# ADE7753.net
KiCad netlist of a schematic drawn in Altium Designer
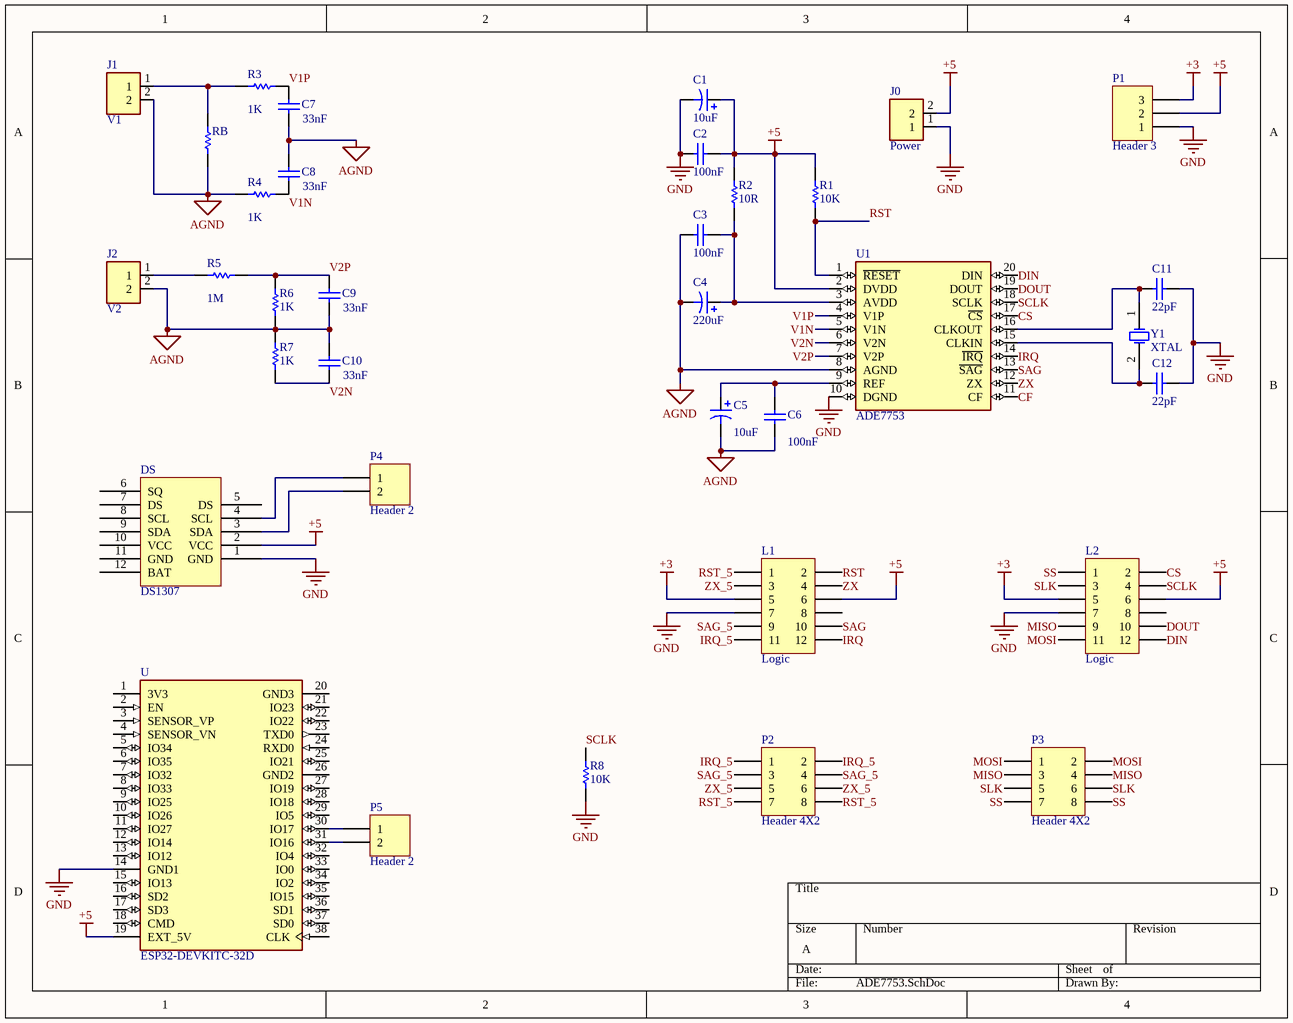
[diagram p0: ADE7753.SchDoc]

(export (version "E")
  (design (tool "Eeschema 10.0.6"))
  (components
    (comp (ref "C1")
      (value "10uF")
      (footprint "Tu hóa 10uF 50v")
      (description "Polarized Capacitor (Radial)")
      (fields (field (name "Comment") "Cap Pol1") (field (name "PUBLISHER") "Altium Limited"))
      (libsource (lib "Miscellaneous Devices") (part "Cap Pol1"))
    )
    (comp (ref "C2")
      (value "100nF")
      (footprint "Tu Gom")
      (description "Capacitor")
      (fields (field (name "Comment") "Cap") (field (name "PUBLISHER") "Altium Limited"))
      (libsource (lib "Miscellaneous Devices") (part "Cap"))
    )
    (comp (ref "C3")
      (value "100nF")
      (footprint "Tu Gom")
      (description "Capacitor")
      (fields (field (name "Comment") "Cap") (field (name "PUBLISHER") "Altium Limited"))
      (libsource (lib "Miscellaneous Devices") (part "Cap"))
    )
    (comp (ref "C4")
      (value "220uF")
      (footprint "Tu hóa 10uF 50v")
      (description "Polarized Capacitor (Radial)")
      (fields (field (name "Comment") "Cap Pol1") (field (name "PUBLISHER") "Altium Limited"))
      (libsource (lib "Miscellaneous Devices") (part "Cap Pol1"))
    )
    (comp (ref "C5")
      (value "10uF")
      (footprint "Tu hóa 10uF 50v")
      (description "Polarized Capacitor (Radial)")
      (fields (field (name "Comment") "Cap Pol1") (field (name "PUBLISHER") "Altium Limited"))
      (libsource (lib "Miscellaneous Devices") (part "Cap Pol1"))
    )
    (comp (ref "C6")
      (value "100nF")
      (footprint "Tu Gom")
      (description "Capacitor")
      (fields (field (name "Comment") "Cap") (field (name "PUBLISHER") "Altium Limited"))
      (libsource (lib "Miscellaneous Devices") (part "Cap"))
    )
    (comp (ref "C7")
      (value "33nF")
      (footprint "Tu Gom")
      (description "Capacitor")
      (fields (field (name "Comment") "Cap") (field (name "PUBLISHER") "Altium Limited"))
      (libsource (lib "Miscellaneous Devices") (part "Cap"))
    )
    (comp (ref "C8")
      (value "33nF")
      (footprint "Tu Gom")
      (description "Capacitor")
      (fields (field (name "Comment") "Cap") (field (name "PUBLISHER") "Altium Limited"))
      (libsource (lib "Miscellaneous Devices") (part "Cap"))
    )
    (comp (ref "C9")
      (value "33nF")
      (footprint "Tu Gom")
      (description "Capacitor")
      (fields (field (name "Comment") "Cap") (field (name "PUBLISHER") "Altium Limited"))
      (libsource (lib "Miscellaneous Devices") (part "Cap"))
    )
    (comp (ref "C10")
      (value "33nF")
      (footprint "Tu Gom")
      (description "Capacitor")
      (fields (field (name "Comment") "Cap") (field (name "PUBLISHER") "Altium Limited"))
      (libsource (lib "Miscellaneous Devices") (part "Cap"))
    )
    (comp (ref "C11")
      (value "22pF")
      (footprint "Tu Gom")
      (description "Capacitor")
      (fields (field (name "Comment") "Cap") (field (name "PUBLISHER") "Altium Limited"))
      (libsource (lib "Miscellaneous Devices") (part "Cap"))
    )
    (comp (ref "C12")
      (value "22pF")
      (footprint "Tu Gom")
      (description "Capacitor")
      (fields (field (name "Comment") "Cap") (field (name "PUBLISHER") "Altium Limited"))
      (libsource (lib "Miscellaneous Devices") (part "Cap"))
    )
    (comp (ref "DS")
      (value "DS1307")
      (footprint "PCBComponent_1")
      (libsource (lib "DS1307") (part "Component_1"))
    )
    (comp (ref "J0")
      (value "Power")
      (footprint "CONN_282836-2")
      (description "TERM BLOCK 2POS SIDE ENTRY 5MM")
      (fields (field (name "MF") "{'manufacturer': u'TE Connectivity'}") (field (name "MP") "282836-2"))
      (libsource (lib "") (part "282836-2_1"))
    )
    (comp (ref "J1")
      (value "V1")
      (footprint "CONN_282836-2")
      (description "TERM BLOCK 2POS SIDE ENTRY 5MM")
      (fields (field (name "MF") "{'manufacturer': u'TE Connectivity'}") (field (name "MP") "282836-2"))
      (libsource (lib "SnapEDA_Library") (part "282836-2"))
    )
    (comp (ref "J2")
      (value "V2")
      (footprint "CONN_282836-2")
      (description "TERM BLOCK 2POS SIDE ENTRY 5MM")
      (fields (field (name "MF") "{'manufacturer': u'TE Connectivity'}") (field (name "MP") "282836-2"))
      (libsource (lib "SnapEDA_Library") (part "282836-2"))
    )
    (comp (ref "L1")
      (value "Logic")
      (footprint "Logic level 3-5")
      (description "Header, 6-Pin, Dual row")
      (fields (field (name "PUBLISHER") "Altium Limited"))
      (libsource (lib "Miscellaneous Connectors") (part "Header 6X2"))
    )
    (comp (ref "L2")
      (value "Logic")
      (footprint "Logic level 3-5")
      (description "Header, 6-Pin, Dual row")
      (fields (field (name "PUBLISHER") "Altium Limited"))
      (libsource (lib "Miscellaneous Connectors") (part "Header 6X2"))
    )
    (comp (ref "P1")
      (value "Header 3")
      (footprint "HDR1X3")
      (description "Header, 3-Pin")
      (fields (field (name "PUBLISHER") "Altium Limited"))
      (libsource (lib "Miscellaneous Connectors") (part "Header 3"))
    )
    (comp (ref "P2")
      (value "Header 4X2")
      (footprint "HDR2X4")
      (description "Header, 4-Pin, Dual row")
      (fields (field (name "PUBLISHER") "Altium Limited"))
      (libsource (lib "Miscellaneous Connectors") (part "Header 4X2"))
    )
    (comp (ref "P3")
      (value "Header 4X2")
      (footprint "HDR2X4")
      (description "Header, 4-Pin, Dual row")
      (fields (field (name "PUBLISHER") "Altium Limited"))
      (libsource (lib "Miscellaneous Connectors") (part "Header 4X2"))
    )
    (comp (ref "P4")
      (value "Header 2")
      (footprint "HDR1X2")
      (description "Header, 2-Pin")
      (fields (field (name "PUBLISHER") "Altium Limited"))
      (libsource (lib "Miscellaneous Connectors") (part "Header 2"))
    )
    (comp (ref "P5")
      (value "Header 2")
      (footprint "HDR1X2")
      (description "Header, 2-Pin")
      (fields (field (name "PUBLISHER") "Altium Limited"))
      (libsource (lib "Miscellaneous Connectors") (part "Header 2"))
    )
    (comp (ref "R1")
      (value "10K")
      (footprint "AXIAL-0.3")
      (description "Resistor")
      (fields (field (name "Comment") "Res1") (field (name "PUBLISHER") "Altium Limited"))
      (libsource (lib "Miscellaneous Devices") (part "Res1"))
    )
    (comp (ref "R2")
      (value "10R")
      (footprint "AXIAL-0.3")
      (description "Resistor")
      (fields (field (name "Comment") "Res1") (field (name "PUBLISHER") "Altium Limited"))
      (libsource (lib "Miscellaneous Devices") (part "Res1"))
    )
    (comp (ref "R3")
      (value "1K")
      (footprint "AXIAL-0.3")
      (description "Resistor")
      (fields (field (name "Comment") "Res1") (field (name "PUBLISHER") "Altium Limited"))
      (libsource (lib "Miscellaneous Devices") (part "Res1"))
    )
    (comp (ref "R4")
      (value "1K")
      (footprint "AXIAL-0.3")
      (description "Resistor")
      (fields (field (name "Comment") "Res1") (field (name "PUBLISHER") "Altium Limited"))
      (libsource (lib "Miscellaneous Devices") (part "Res1"))
    )
    (comp (ref "R5")
      (value "1M")
      (footprint "AXIAL-0.3")
      (description "Resistor")
      (fields (field (name "Comment") "Res1") (field (name "PUBLISHER") "Altium Limited"))
      (libsource (lib "Miscellaneous Devices") (part "Res1"))
    )
    (comp (ref "R6")
      (value "1K")
      (footprint "AXIAL-0.3")
      (description "Resistor")
      (fields (field (name "Comment") "Res1") (field (name "PUBLISHER") "Altium Limited"))
      (libsource (lib "Miscellaneous Devices") (part "Res1"))
    )
    (comp (ref "R7")
      (value "1K")
      (footprint "AXIAL-0.3")
      (description "Resistor")
      (fields (field (name "Comment") "Res1") (field (name "PUBLISHER") "Altium Limited"))
      (libsource (lib "Miscellaneous Devices") (part "Res1"))
    )
    (comp (ref "R8")
      (value "10K")
      (footprint "AXIAL-0.3")
      (description "Resistor")
      (fields (field (name "Comment") "Res1") (field (name "PUBLISHER") "Altium Limited"))
      (libsource (lib "Miscellaneous Devices") (part "Res1"))
    )
    (comp (ref "RB")
      (value "Res1")
      (footprint "AXIAL-0.3")
      (description "Resistor")
      (fields (field (name "PUBLISHER") "Altium Limited"))
      (libsource (lib "Miscellaneous Devices") (part "Res1"))
    )
    (comp (ref "U")
      (value "ESP32-DEVKITC-32D")
      (footprint "MODULE_ESP32-DEVKITC-32D")
      (fields (field (name "MF") "Espressif Systems"))
      (libsource (lib "ESP32-DEVKITC-32D") (part "ESP32-DEVKITC-32D"))
    )
    (comp (ref "U1")
      (value "ADE7753")
      (footprint "ADE_Header")
      (description "Single-Phase Multifunction Metering IC")
      (fields (field (name "MF") "{'manufacturer': u'Analog Devices'}"))
      (libsource (lib "SnapEDA_Library") (part "ADE7753"))
    )
    (comp (ref "Y1")
      (value "XTAL")
      (footprint "3.5795 mhz crystal")
      (description "Crystal Oscillator")
      (fields (field (name "PUBLISHER") "Altium Limited"))
      (libsource (lib "Miscellaneous Devices") (part "XTAL"))
    )
  )
  (nets
    (net (code "1") (name "+3") (class "Default")
      (node (ref "L1") (pin "5") (pinfunction "5_5") (pintype "passive"))
      (node (ref "L2") (pin "5") (pinfunction "5_5") (pintype "passive"))
      (node (ref "P1") (pin "3") (pinfunction "3_3") (pintype "passive"))
    )
    (net (code "2") (name "+5") (class "Default")
      (node (ref "C1") (pin "1") (pinfunction "1_1") (pintype "passive"))
      (node (ref "C2") (pin "1") (pinfunction "1_1") (pintype "passive"))
      (node (ref "DS") (pin "2") (pinfunction "VCC_2") (pintype "passive"))
      (node (ref "J0") (pin "2") (pinfunction "2_2") (pintype "passive"))
      (node (ref "L1") (pin "6") (pinfunction "6_6") (pintype "passive"))
      (node (ref "L2") (pin "6") (pinfunction "6_6") (pintype "passive"))
      (node (ref "P1") (pin "2") (pinfunction "2_2") (pintype "passive"))
      (node (ref "R1") (pin "2") (pinfunction "2_2") (pintype "passive"))
      (node (ref "R2") (pin "2") (pinfunction "2_2") (pintype "passive"))
      (node (ref "U") (pin "19") (pinfunction "EXT_5V_19") (pintype "power_in"))
      (node (ref "U1") (pin "2") (pinfunction "DVDD_2") (pintype "bidirectional"))
    )
    (net (code "3") (name "/CF") (class "Default")
      (node (ref "U1") (pin "11") (pinfunction "CF_11") (pintype "bidirectional"))
    )
    (net (code "4") (name "/CS") (class "Default")
      (node (ref "L2") (pin "2") (pinfunction "2_2") (pintype "passive"))
      (node (ref "U1") (pin "17") (pinfunction "~{CS}_17") (pintype "bidirectional"))
    )
    (net (code "5") (name "/DIN") (class "Default")
      (node (ref "L2") (pin "12") (pinfunction "12_12") (pintype "passive"))
      (node (ref "U1") (pin "20") (pinfunction "DIN_20") (pintype "bidirectional"))
    )
    (net (code "6") (name "/DOUT") (class "Default")
      (node (ref "L2") (pin "10") (pinfunction "10_10") (pintype "passive"))
      (node (ref "U1") (pin "19") (pinfunction "DOUT_19") (pintype "bidirectional"))
    )
    (net (code "7") (name "/IRQ") (class "Default")
      (node (ref "L1") (pin "12") (pinfunction "12_12") (pintype "passive"))
      (node (ref "U1") (pin "14") (pinfunction "~{IRQ}_14") (pintype "bidirectional"))
    )
    (net (code "8") (name "/IRQ_5") (class "Default")
      (node (ref "L1") (pin "11") (pinfunction "11_11") (pintype "passive"))
      (node (ref "P2") (pin "1") (pinfunction "1_1") (pintype "passive"))
      (node (ref "P2") (pin "2") (pinfunction "2_2") (pintype "passive"))
    )
    (net (code "9") (name "/MISO") (class "Default")
      (node (ref "L2") (pin "9") (pinfunction "9_9") (pintype "passive"))
      (node (ref "P3") (pin "3") (pinfunction "3_3") (pintype "passive"))
      (node (ref "P3") (pin "4") (pinfunction "4_4") (pintype "passive"))
    )
    (net (code "10") (name "/MOSI") (class "Default")
      (node (ref "L2") (pin "11") (pinfunction "11_11") (pintype "passive"))
      (node (ref "P3") (pin "1") (pinfunction "1_1") (pintype "passive"))
      (node (ref "P3") (pin "2") (pinfunction "2_2") (pintype "passive"))
    )
    (net (code "11") (name "/RST") (class "Default")
      (node (ref "L1") (pin "2") (pinfunction "2_2") (pintype "passive"))
      (node (ref "R1") (pin "1") (pinfunction "1_1") (pintype "passive"))
      (node (ref "U1") (pin "1") (pinfunction "~{RESET}_1") (pintype "bidirectional"))
    )
    (net (code "12") (name "/RST_5") (class "Default")
      (node (ref "L1") (pin "1") (pinfunction "1_1") (pintype "passive"))
      (node (ref "P2") (pin "7") (pinfunction "7_7") (pintype "passive"))
      (node (ref "P2") (pin "8") (pinfunction "8_8") (pintype "passive"))
    )
    (net (code "13") (name "/SAG") (class "Default")
      (node (ref "L1") (pin "10") (pinfunction "10_10") (pintype "passive"))
      (node (ref "U1") (pin "13") (pinfunction "~{SAG}_13") (pintype "bidirectional"))
    )
    (net (code "14") (name "/SAG_5") (class "Default")
      (node (ref "L1") (pin "9") (pinfunction "9_9") (pintype "passive"))
      (node (ref "P2") (pin "3") (pinfunction "3_3") (pintype "passive"))
      (node (ref "P2") (pin "4") (pinfunction "4_4") (pintype "passive"))
    )
    (net (code "15") (name "/SCLK") (class "Default")
      (node (ref "L2") (pin "4") (pinfunction "4_4") (pintype "passive"))
      (node (ref "R8") (pin "2") (pinfunction "2_2") (pintype "passive"))
      (node (ref "U1") (pin "18") (pinfunction "SCLK_18") (pintype "bidirectional"))
    )
    (net (code "16") (name "/SLK") (class "Default")
      (node (ref "L2") (pin "3") (pinfunction "3_3") (pintype "passive"))
      (node (ref "P3") (pin "5") (pinfunction "5_5") (pintype "passive"))
      (node (ref "P3") (pin "6") (pinfunction "6_6") (pintype "passive"))
    )
    (net (code "17") (name "/SS") (class "Default")
      (node (ref "L2") (pin "1") (pinfunction "1_1") (pintype "passive"))
      (node (ref "P3") (pin "7") (pinfunction "7_7") (pintype "passive"))
      (node (ref "P3") (pin "8") (pinfunction "8_8") (pintype "passive"))
    )
    (net (code "18") (name "/V1N") (class "Default")
      (node (ref "C8") (pin "1") (pinfunction "1_1") (pintype "passive"))
      (node (ref "R4") (pin "2") (pinfunction "2_2") (pintype "passive"))
      (node (ref "U1") (pin "5") (pinfunction "V1N_5") (pintype "bidirectional"))
    )
    (net (code "19") (name "/V1P") (class "Default")
      (node (ref "C7") (pin "2") (pinfunction "2_2") (pintype "passive"))
      (node (ref "R3") (pin "2") (pinfunction "2_2") (pintype "passive"))
      (node (ref "U1") (pin "4") (pinfunction "V1P_4") (pintype "bidirectional"))
    )
    (net (code "20") (name "/V2N") (class "Default")
      (node (ref "C10") (pin "1") (pinfunction "1_1") (pintype "passive"))
      (node (ref "R7") (pin "1") (pinfunction "1_1") (pintype "passive"))
      (node (ref "U1") (pin "6") (pinfunction "V2N_6") (pintype "bidirectional"))
    )
    (net (code "21") (name "/V2P") (class "Default")
      (node (ref "C9") (pin "2") (pinfunction "2_2") (pintype "passive"))
      (node (ref "R5") (pin "2") (pinfunction "2_2") (pintype "passive"))
      (node (ref "R6") (pin "2") (pinfunction "2_2") (pintype "passive"))
      (node (ref "U1") (pin "7") (pinfunction "V2P_7") (pintype "bidirectional"))
    )
    (net (code "22") (name "/ZX") (class "Default")
      (node (ref "L1") (pin "4") (pinfunction "4_4") (pintype "passive"))
      (node (ref "U1") (pin "12") (pinfunction "ZX_12") (pintype "bidirectional"))
    )
    (net (code "23") (name "/ZX_5") (class "Default")
      (node (ref "L1") (pin "3") (pinfunction "3_3") (pintype "passive"))
      (node (ref "P2") (pin "5") (pinfunction "5_5") (pintype "passive"))
      (node (ref "P2") (pin "6") (pinfunction "6_6") (pintype "passive"))
    )
    (net (code "24") (name "AGND") (class "Default")
      (node (ref "C10") (pin "2") (pinfunction "2_2") (pintype "passive"))
      (node (ref "C3") (pin "2") (pinfunction "2_2") (pintype "passive"))
      (node (ref "C4") (pin "2") (pinfunction "2_2") (pintype "passive"))
      (node (ref "C5") (pin "2") (pinfunction "2_2") (pintype "passive"))
      (node (ref "C6") (pin "1") (pinfunction "1_1") (pintype "passive"))
      (node (ref "C7") (pin "1") (pinfunction "1_1") (pintype "passive"))
      (node (ref "C8") (pin "2") (pinfunction "2_2") (pintype "passive"))
      (node (ref "C9") (pin "1") (pinfunction "1_1") (pintype "passive"))
      (node (ref "J1") (pin "2") (pinfunction "2_2") (pintype "passive"))
      (node (ref "J2") (pin "2") (pinfunction "2_2") (pintype "passive"))
      (node (ref "R4") (pin "1") (pinfunction "1_1") (pintype "passive"))
      (node (ref "R6") (pin "1") (pinfunction "1_1") (pintype "passive"))
      (node (ref "R7") (pin "2") (pinfunction "2_2") (pintype "passive"))
      (node (ref "RB") (pin "1") (pinfunction "1_1") (pintype "passive"))
      (node (ref "U1") (pin "8") (pinfunction "AGND_8") (pintype "bidirectional"))
    )
    (net (code "25") (name "GND") (class "Default")
      (node (ref "C1") (pin "2") (pinfunction "2_2") (pintype "passive"))
      (node (ref "C11") (pin "1") (pinfunction "1_1") (pintype "passive"))
      (node (ref "C12") (pin "1") (pinfunction "1_1") (pintype "passive"))
      (node (ref "C2") (pin "2") (pinfunction "2_2") (pintype "passive"))
      (node (ref "DS") (pin "1") (pinfunction "GND_1") (pintype "passive"))
      (node (ref "J0") (pin "1") (pinfunction "1_1") (pintype "passive"))
      (node (ref "L1") (pin "7") (pinfunction "7_7") (pintype "passive"))
      (node (ref "L2") (pin "7") (pinfunction "7_7") (pintype "passive"))
      (node (ref "P1") (pin "1") (pinfunction "1_1") (pintype "passive"))
      (node (ref "R8") (pin "1") (pinfunction "1_1") (pintype "passive"))
      (node (ref "U") (pin "14") (pinfunction "GND1_14") (pintype "power_in"))
      (node (ref "U1") (pin "10") (pinfunction "DGND_10") (pintype "bidirectional"))
    )
    (net (code "26") (name "Net-(DS-SCL-Pad4)") (class "Default")
      (node (ref "DS") (pin "4") (pinfunction "SCL_4") (pintype "passive"))
      (node (ref "P4") (pin "1") (pinfunction "1_1") (pintype "passive"))
    )
    (net (code "27") (name "Net-(DS-SDA-Pad3)") (class "Default")
      (node (ref "DS") (pin "3") (pinfunction "SDA_3") (pintype "passive"))
      (node (ref "P4") (pin "2") (pinfunction "2_2") (pintype "passive"))
    )
    (net (code "28") (name "Net-(J1-Pad1)") (class "Default")
      (node (ref "J1") (pin "1") (pinfunction "1_1") (pintype "passive"))
      (node (ref "R3") (pin "1") (pinfunction "1_1") (pintype "passive"))
      (node (ref "RB") (pin "2") (pinfunction "2_2") (pintype "passive"))
    )
    (net (code "29") (name "Net-(J2-Pad1)") (class "Default")
      (node (ref "J2") (pin "1") (pinfunction "1_1") (pintype "passive"))
      (node (ref "R5") (pin "1") (pinfunction "1_1") (pintype "passive"))
    )
    (net (code "30") (name "Net-(U-IO16)") (class "Default")
      (node (ref "P5") (pin "2") (pinfunction "2_2") (pintype "passive"))
      (node (ref "U") (pin "31") (pinfunction "IO16_31") (pintype "bidirectional"))
    )
    (net (code "31") (name "Net-(U-IO17)") (class "Default")
      (node (ref "P5") (pin "1") (pinfunction "1_1") (pintype "passive"))
      (node (ref "U") (pin "30") (pinfunction "IO17_30") (pintype "bidirectional"))
    )
    (net (code "32") (name "Net-(U1-AVDD)") (class "Default")
      (node (ref "C3") (pin "1") (pinfunction "1_1") (pintype "passive"))
      (node (ref "C4") (pin "1") (pinfunction "1_1") (pintype "passive"))
      (node (ref "R2") (pin "1") (pinfunction "1_1") (pintype "passive"))
      (node (ref "U1") (pin "3") (pinfunction "AVDD_3") (pintype "bidirectional"))
    )
    (net (code "33") (name "Net-(U1-CLKIN)") (class "Default")
      (node (ref "C12") (pin "2") (pinfunction "2_2") (pintype "passive"))
      (node (ref "U1") (pin "15") (pinfunction "CLKIN_15") (pintype "bidirectional"))
      (node (ref "Y1") (pin "2") (pinfunction "OSC2_2") (pintype "passive"))
    )
    (net (code "34") (name "Net-(U1-CLKOUT)") (class "Default")
      (node (ref "C11") (pin "2") (pinfunction "2_2") (pintype "passive"))
      (node (ref "U1") (pin "16") (pinfunction "CLKOUT_16") (pintype "bidirectional"))
      (node (ref "Y1") (pin "1") (pinfunction "OSC1_1") (pintype "passive"))
    )
    (net (code "35") (name "Net-(U1-REF)") (class "Default")
      (node (ref "C5") (pin "1") (pinfunction "1_1") (pintype "passive"))
      (node (ref "C6") (pin "2") (pinfunction "2_2") (pintype "passive"))
      (node (ref "U1") (pin "9") (pinfunction "REF_9") (pintype "bidirectional"))
    )
    (net (code "36") (name "unconnected-(DS-BAT-Pad12)") (class "Default")
      (node (ref "DS") (pin "12") (pinfunction "BAT_12") (pintype "passive"))
    )
    (net (code "37") (name "unconnected-(DS-DS-Pad5)") (class "Default")
      (node (ref "DS") (pin "5") (pinfunction "DS_5") (pintype "passive"))
    )
    (net (code "38") (name "unconnected-(DS-DS-Pad7)") (class "Default")
      (node (ref "DS") (pin "7") (pinfunction "DS_7") (pintype "passive"))
    )
    (net (code "39") (name "unconnected-(DS-GND-Pad11)") (class "Default")
      (node (ref "DS") (pin "11") (pinfunction "GND_11") (pintype "passive"))
    )
    (net (code "40") (name "unconnected-(DS-SCL-Pad8)") (class "Default")
      (node (ref "DS") (pin "8") (pinfunction "SCL_8") (pintype "passive"))
    )
    (net (code "41") (name "unconnected-(DS-SDA-Pad9)") (class "Default")
      (node (ref "DS") (pin "9") (pinfunction "SDA_9") (pintype "passive"))
    )
    (net (code "42") (name "unconnected-(DS-SQ-Pad6)") (class "Default")
      (node (ref "DS") (pin "6") (pinfunction "SQ_6") (pintype "passive"))
    )
    (net (code "43") (name "unconnected-(DS-VCC-Pad10)") (class "Default")
      (node (ref "DS") (pin "10") (pinfunction "VCC_10") (pintype "passive"))
    )
    (net (code "44") (name "unconnected-(L1-Pad8)") (class "Default")
      (node (ref "L1") (pin "8") (pinfunction "8_8") (pintype "passive"))
    )
    (net (code "45") (name "unconnected-(L2-Pad8)") (class "Default")
      (node (ref "L2") (pin "8") (pinfunction "8_8") (pintype "passive"))
    )
    (net (code "46") (name "unconnected-(U-3V3-Pad1)") (class "Default")
      (node (ref "U") (pin "1") (pinfunction "3V3_1") (pintype "power_in"))
    )
    (net (code "47") (name "unconnected-(U-CLK-Pad38)") (class "Default")
      (node (ref "U") (pin "38") (pinfunction "CLK_38") (pintype "input"))
    )
    (net (code "48") (name "unconnected-(U-CMD-Pad18)") (class "Default")
      (node (ref "U") (pin "18") (pinfunction "CMD_18") (pintype "bidirectional"))
    )
    (net (code "49") (name "unconnected-(U-EN-Pad2)") (class "Default")
      (node (ref "U") (pin "2") (pinfunction "EN_2") (pintype "input"))
    )
    (net (code "50") (name "unconnected-(U-GND2-Pad26)") (class "Default")
      (node (ref "U") (pin "26") (pinfunction "GND2_26") (pintype "power_in"))
    )
    (net (code "51") (name "unconnected-(U-GND3-Pad20)") (class "Default")
      (node (ref "U") (pin "20") (pinfunction "GND3_20") (pintype "power_in"))
    )
    (net (code "52") (name "unconnected-(U-IO0-Pad33)") (class "Default")
      (node (ref "U") (pin "33") (pinfunction "IO0_33") (pintype "bidirectional"))
    )
    (net (code "53") (name "unconnected-(U-IO2-Pad34)") (class "Default")
      (node (ref "U") (pin "34") (pinfunction "IO2_34") (pintype "bidirectional"))
    )
    (net (code "54") (name "unconnected-(U-IO4-Pad32)") (class "Default")
      (node (ref "U") (pin "32") (pinfunction "IO4_32") (pintype "bidirectional"))
    )
    (net (code "55") (name "unconnected-(U-IO5-Pad29)") (class "Default")
      (node (ref "U") (pin "29") (pinfunction "IO5_29") (pintype "bidirectional"))
    )
    (net (code "56") (name "unconnected-(U-IO12-Pad13)") (class "Default")
      (node (ref "U") (pin "13") (pinfunction "IO12_13") (pintype "bidirectional"))
    )
    (net (code "57") (name "unconnected-(U-IO13-Pad15)") (class "Default")
      (node (ref "U") (pin "15") (pinfunction "IO13_15") (pintype "bidirectional"))
    )
    (net (code "58") (name "unconnected-(U-IO14-Pad12)") (class "Default")
      (node (ref "U") (pin "12") (pinfunction "IO14_12") (pintype "bidirectional"))
    )
    (net (code "59") (name "unconnected-(U-IO15-Pad35)") (class "Default")
      (node (ref "U") (pin "35") (pinfunction "IO15_35") (pintype "bidirectional"))
    )
    (net (code "60") (name "unconnected-(U-IO18-Pad28)") (class "Default")
      (node (ref "U") (pin "28") (pinfunction "IO18_28") (pintype "bidirectional"))
    )
    (net (code "61") (name "unconnected-(U-IO19-Pad27)") (class "Default")
      (node (ref "U") (pin "27") (pinfunction "IO19_27") (pintype "bidirectional"))
    )
    (net (code "62") (name "unconnected-(U-IO21-Pad25)") (class "Default")
      (node (ref "U") (pin "25") (pinfunction "IO21_25") (pintype "bidirectional"))
    )
    (net (code "63") (name "unconnected-(U-IO22-Pad22)") (class "Default")
      (node (ref "U") (pin "22") (pinfunction "IO22_22") (pintype "bidirectional"))
    )
    (net (code "64") (name "unconnected-(U-IO23-Pad21)") (class "Default")
      (node (ref "U") (pin "21") (pinfunction "IO23_21") (pintype "bidirectional"))
    )
    (net (code "65") (name "unconnected-(U-IO25-Pad9)") (class "Default")
      (node (ref "U") (pin "9") (pinfunction "IO25_9") (pintype "bidirectional"))
    )
    (net (code "66") (name "unconnected-(U-IO26-Pad10)") (class "Default")
      (node (ref "U") (pin "10") (pinfunction "IO26_10") (pintype "bidirectional"))
    )
    (net (code "67") (name "unconnected-(U-IO27-Pad11)") (class "Default")
      (node (ref "U") (pin "11") (pinfunction "IO27_11") (pintype "bidirectional"))
    )
    (net (code "68") (name "unconnected-(U-IO32-Pad7)") (class "Default")
      (node (ref "U") (pin "7") (pinfunction "IO32_7") (pintype "bidirectional"))
    )
    (net (code "69") (name "unconnected-(U-IO33-Pad8)") (class "Default")
      (node (ref "U") (pin "8") (pinfunction "IO33_8") (pintype "bidirectional"))
    )
    (net (code "70") (name "unconnected-(U-IO34-Pad5)") (class "Default")
      (node (ref "U") (pin "5") (pinfunction "IO34_5") (pintype "bidirectional"))
    )
    (net (code "71") (name "unconnected-(U-IO35-Pad6)") (class "Default")
      (node (ref "U") (pin "6") (pinfunction "IO35_6") (pintype "bidirectional"))
    )
    (net (code "72") (name "unconnected-(U-RXD0-Pad24)") (class "Default")
      (node (ref "U") (pin "24") (pinfunction "RXD0_24") (pintype "input"))
    )
    (net (code "73") (name "unconnected-(U-SD0-Pad37)") (class "Default")
      (node (ref "U") (pin "37") (pinfunction "SD0_37") (pintype "bidirectional"))
    )
    (net (code "74") (name "unconnected-(U-SD1-Pad36)") (class "Default")
      (node (ref "U") (pin "36") (pinfunction "SD1_36") (pintype "bidirectional"))
    )
    (net (code "75") (name "unconnected-(U-SD2-Pad16)") (class "Default")
      (node (ref "U") (pin "16") (pinfunction "SD2_16") (pintype "bidirectional"))
    )
    (net (code "76") (name "unconnected-(U-SD3-Pad17)") (class "Default")
      (node (ref "U") (pin "17") (pinfunction "SD3_17") (pintype "bidirectional"))
    )
    (net (code "77") (name "unconnected-(U-SENSOR_VN-Pad4)") (class "Default")
      (node (ref "U") (pin "4") (pinfunction "SENSOR_VN_4") (pintype "input"))
    )
    (net (code "78") (name "unconnected-(U-SENSOR_VP-Pad3)") (class "Default")
      (node (ref "U") (pin "3") (pinfunction "SENSOR_VP_3") (pintype "input"))
    )
    (net (code "79") (name "unconnected-(U-TXD0-Pad23)") (class "Default")
      (node (ref "U") (pin "23") (pinfunction "TXD0_23") (pintype "output"))
    )
  )
)
